# E-piano.net
KiCad netlist of a schematic drawn in EAGLE
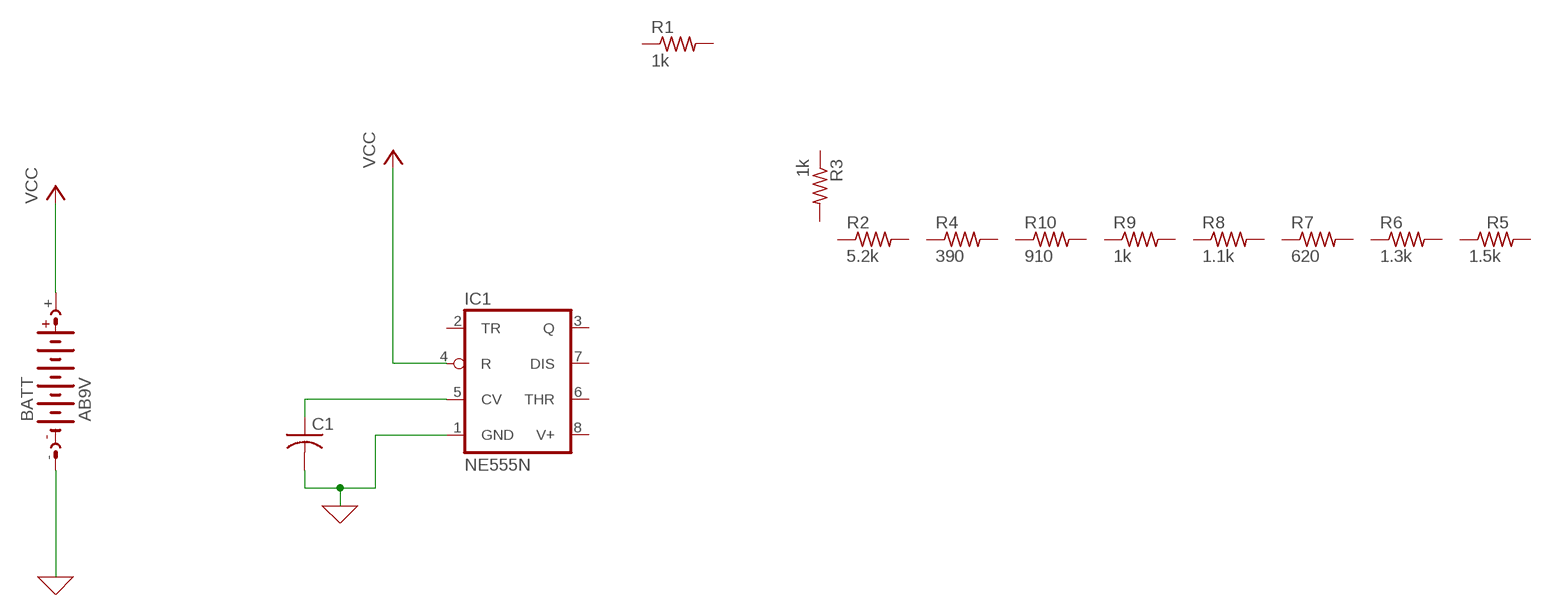
[diagram p0: schematic, sheet 1]

(export (version "E")
  (design (tool "Eeschema 10.0.6"))
  (components
    (comp (ref "BATT")
      (value "AB9V")
      (footprint "eagle-import:AB9V")
      (libsource (lib "eagle-import") (part "AB9V"))
    )
    (comp (ref "C1")
      (value "C-US025-025X050")
      (footprint "eagle-import:C025-025X050")
      (libsource (lib "eagle-import") (part "C-US025-025X050"))
    )
    (comp (ref "IC1")
      (value "NE555N")
      (footprint "eagle-import:DIL08")
      (libsource (lib "eagle-import") (part "555NNE"))
    )
    (comp (ref "R1")
      (value "1k")
      (footprint "eagle-import:0207_10")
      (libsource (lib "eagle-import") (part "R-US_0207/10"))
    )
    (comp (ref "R2")
      (value "5.2k")
      (footprint "eagle-import:0207_10")
      (libsource (lib "eagle-import") (part "R-US_0207/10"))
    )
    (comp (ref "R3")
      (value "1k")
      (footprint "eagle-import:0207_10")
      (libsource (lib "eagle-import") (part "R-US_0207/10"))
    )
    (comp (ref "R4")
      (value "390")
      (footprint "eagle-import:0207_10")
      (libsource (lib "eagle-import") (part "R-US_0207/10"))
    )
    (comp (ref "R5")
      (value "1.5k")
      (footprint "eagle-import:0207_10")
      (libsource (lib "eagle-import") (part "R-US_0207/10"))
    )
    (comp (ref "R6")
      (value "1.3k")
      (footprint "eagle-import:0207_10")
      (libsource (lib "eagle-import") (part "R-US_0207/10"))
    )
    (comp (ref "R7")
      (value "620")
      (footprint "eagle-import:0207_10")
      (libsource (lib "eagle-import") (part "R-US_0207/10"))
    )
    (comp (ref "R8")
      (value "1.1k")
      (footprint "eagle-import:0207_10")
      (libsource (lib "eagle-import") (part "R-US_0207/10"))
    )
    (comp (ref "R9")
      (value "1k")
      (footprint "eagle-import:0207_10")
      (libsource (lib "eagle-import") (part "R-US_0207/10"))
    )
    (comp (ref "R10")
      (value "910")
      (footprint "eagle-import:0207_10")
      (libsource (lib "eagle-import") (part "R-US_0207/10"))
    )
  )
  (nets
    (net (code "1") (name "/V+") (class "Default")
      (node (ref "IC1") (pin "8") (pinfunction "V+_8") (pintype "power_in"))
    )
    (net (code "2") (name "GND") (class "Default")
      (node (ref "BATT") (pin "-") (pinfunction "-_-") (pintype "passive"))
      (node (ref "C1") (pin "2") (pinfunction "2_2") (pintype "passive"))
      (node (ref "IC1") (pin "1") (pinfunction "GND_1") (pintype "power_in"))
    )
    (net (code "3") (name "Net-(IC1-CV)") (class "Default")
      (node (ref "C1") (pin "1") (pinfunction "1_1") (pintype "passive"))
      (node (ref "IC1") (pin "5") (pinfunction "CV_5") (pintype "input"))
    )
    (net (code "4") (name "VCC") (class "Default")
      (node (ref "BATT") (pin "+") (pinfunction "+_+") (pintype "passive"))
      (node (ref "IC1") (pin "4") (pinfunction "R_4") (pintype "input"))
    )
    (net (code "5") (name "unconnected-(IC1-DIS-Pad7)") (class "Default")
      (node (ref "IC1") (pin "7") (pinfunction "DIS_7") (pintype "input"))
    )
    (net (code "6") (name "unconnected-(IC1-Q-Pad3)") (class "Default")
      (node (ref "IC1") (pin "3") (pinfunction "Q_3") (pintype "output"))
    )
    (net (code "7") (name "unconnected-(IC1-THR-Pad6)") (class "Default")
      (node (ref "IC1") (pin "6") (pinfunction "THR_6") (pintype "input"))
    )
    (net (code "8") (name "unconnected-(IC1-TR-Pad2)") (class "Default")
      (node (ref "IC1") (pin "2") (pinfunction "TR_2") (pintype "input"))
    )
    (net (code "9") (name "unconnected-(R1-Pad1)") (class "Default")
      (node (ref "R1") (pin "1") (pinfunction "1_1") (pintype "passive"))
    )
    (net (code "10") (name "unconnected-(R1-Pad2)") (class "Default")
      (node (ref "R1") (pin "2") (pinfunction "2_2") (pintype "passive"))
    )
    (net (code "11") (name "unconnected-(R2-Pad1)") (class "Default")
      (node (ref "R2") (pin "1") (pinfunction "1_1") (pintype "passive"))
    )
    (net (code "12") (name "unconnected-(R2-Pad2)") (class "Default")
      (node (ref "R2") (pin "2") (pinfunction "2_2") (pintype "passive"))
    )
    (net (code "13") (name "unconnected-(R3-Pad1)") (class "Default")
      (node (ref "R3") (pin "1") (pinfunction "1_1") (pintype "passive"))
    )
    (net (code "14") (name "unconnected-(R3-Pad2)") (class "Default")
      (node (ref "R3") (pin "2") (pinfunction "2_2") (pintype "passive"))
    )
    (net (code "15") (name "unconnected-(R4-Pad1)") (class "Default")
      (node (ref "R4") (pin "1") (pinfunction "1_1") (pintype "passive"))
    )
    (net (code "16") (name "unconnected-(R4-Pad2)") (class "Default")
      (node (ref "R4") (pin "2") (pinfunction "2_2") (pintype "passive"))
    )
    (net (code "17") (name "unconnected-(R5-Pad1)") (class "Default")
      (node (ref "R5") (pin "1") (pinfunction "1_1") (pintype "passive"))
    )
    (net (code "18") (name "unconnected-(R5-Pad2)") (class "Default")
      (node (ref "R5") (pin "2") (pinfunction "2_2") (pintype "passive"))
    )
    (net (code "19") (name "unconnected-(R6-Pad1)") (class "Default")
      (node (ref "R6") (pin "1") (pinfunction "1_1") (pintype "passive"))
    )
    (net (code "20") (name "unconnected-(R6-Pad2)") (class "Default")
      (node (ref "R6") (pin "2") (pinfunction "2_2") (pintype "passive"))
    )
    (net (code "21") (name "unconnected-(R7-Pad1)") (class "Default")
      (node (ref "R7") (pin "1") (pinfunction "1_1") (pintype "passive"))
    )
    (net (code "22") (name "unconnected-(R7-Pad2)") (class "Default")
      (node (ref "R7") (pin "2") (pinfunction "2_2") (pintype "passive"))
    )
    (net (code "23") (name "unconnected-(R8-Pad1)") (class "Default")
      (node (ref "R8") (pin "1") (pinfunction "1_1") (pintype "passive"))
    )
    (net (code "24") (name "unconnected-(R8-Pad2)") (class "Default")
      (node (ref "R8") (pin "2") (pinfunction "2_2") (pintype "passive"))
    )
    (net (code "25") (name "unconnected-(R9-Pad1)") (class "Default")
      (node (ref "R9") (pin "1") (pinfunction "1_1") (pintype "passive"))
    )
    (net (code "26") (name "unconnected-(R9-Pad2)") (class "Default")
      (node (ref "R9") (pin "2") (pinfunction "2_2") (pintype "passive"))
    )
    (net (code "27") (name "unconnected-(R10-Pad1)") (class "Default")
      (node (ref "R10") (pin "1") (pinfunction "1_1") (pintype "passive"))
    )
    (net (code "28") (name "unconnected-(R10-Pad2)") (class "Default")
      (node (ref "R10") (pin "2") (pinfunction "2_2") (pintype "passive"))
    )
  )
)
